# Sheet1.net
KiCad netlist of a schematic drawn in Altium Designer
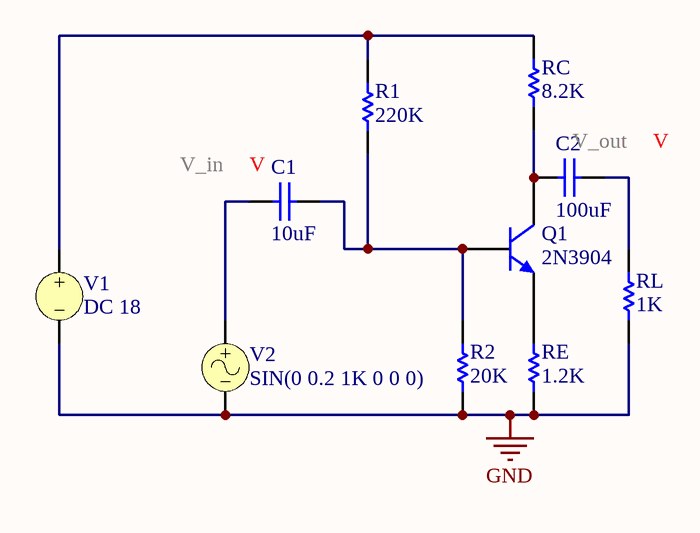
[diagram p0: Sheet1.SchDoc]

(export (version "E")
  (design (tool "Eeschema 10.0.6"))
  (components
    (comp (ref "C1")
      (value "10uF")
      (footprint "RAD-0.3")
      (description "Capacitor")
      (fields (field (name "PUBLISHER") "Altium Limited"))
      (libsource (lib "Miscellaneous Devices") (part "Cap"))
    )
    (comp (ref "C2")
      (value "100uF")
      (footprint "RAD-0.3")
      (description "Capacitor")
      (fields (field (name "PUBLISHER") "Altium Limited"))
      (libsource (lib "Miscellaneous Devices") (part "Cap"))
    )
    (comp (ref "Q1")
      (value "2N3904")
      (footprint "TO-92A")
      (description "NPN General Purpose Amplifier")
      (fields (field (name "PUBLISHER") "Altium Limited"))
      (libsource (lib "Miscellaneous Devices") (part "2N3904"))
    )
    (comp (ref "R1")
      (value "220K")
      (footprint "AXIAL-0.3")
      (description "Resistor")
      (fields (field (name "PUBLISHER") "Altium Limited"))
      (libsource (lib "Miscellaneous Devices") (part "Res1"))
    )
    (comp (ref "R2")
      (value "20K")
      (footprint "AXIAL-0.3")
      (description "Resistor")
      (fields (field (name "PUBLISHER") "Altium Limited"))
      (libsource (lib "Miscellaneous Devices") (part "Res1"))
    )
    (comp (ref "RC")
      (value "8.2K")
      (footprint "AXIAL-0.3")
      (description "Resistor")
      (fields (field (name "PUBLISHER") "Altium Limited"))
      (libsource (lib "Miscellaneous Devices") (part "Res1"))
    )
    (comp (ref "RE")
      (value "1.2K")
      (footprint "AXIAL-0.3")
      (description "Resistor")
      (fields (field (name "PUBLISHER") "Altium Limited"))
      (libsource (lib "Miscellaneous Devices") (part "Res1"))
    )
    (comp (ref "RL")
      (value "1K")
      (footprint "AXIAL-0.3")
      (description "Resistor")
      (fields (field (name "PUBLISHER") "Altium Limited"))
      (libsource (lib "Miscellaneous Devices") (part "Res1"))
    )
    (comp (ref "V1")
      (value "DC 18")
      (description "Voltage Source")
      (fields (field (name "PUBLISHER") "Altium Limited"))
      (libsource (lib "Simulation Generic Components") (part "VSRC"))
    )
    (comp (ref "V2")
      (value "SIN(0 0.2 1K 0 0 0)")
      (description "Sinusoidal Voltage Source")
      (fields (field (name "PUBLISHER") "Altium Limited"))
      (libsource (lib "Simulation Generic Components") (part "VSIN"))
    )
  )
  (nets
    (net (code "1") (name "GND") (class "Default")
      (node (ref "R2") (pin "1") (pinfunction "1_1") (pintype "passive"))
      (node (ref "RE") (pin "1") (pinfunction "1_1") (pintype "passive"))
      (node (ref "RL") (pin "1") (pinfunction "1_1") (pintype "passive"))
      (node (ref "V1") (pin "2") (pinfunction "2_2") (pintype "passive"))
      (node (ref "V2") (pin "2") (pinfunction "2_2") (pintype "passive"))
    )
    (net (code "2") (name "Net-(C1-Pad1)") (class "Default")
      (node (ref "C1") (pin "1") (pinfunction "1_1") (pintype "passive"))
      (node (ref "V2") (pin "1") (pinfunction "1_1") (pintype "passive"))
    )
    (net (code "3") (name "Net-(C2-Pad2)") (class "Default")
      (node (ref "C2") (pin "2") (pinfunction "2_2") (pintype "passive"))
      (node (ref "RL") (pin "2") (pinfunction "2_2") (pintype "passive"))
    )
    (net (code "4") (name "Net-(Q1-B)") (class "Default")
      (node (ref "C1") (pin "2") (pinfunction "2_2") (pintype "passive"))
      (node (ref "Q1") (pin "2") (pinfunction "B_2") (pintype "passive"))
      (node (ref "R1") (pin "1") (pinfunction "1_1") (pintype "passive"))
      (node (ref "R2") (pin "2") (pinfunction "2_2") (pintype "passive"))
    )
    (net (code "5") (name "Net-(Q1-C)") (class "Default")
      (node (ref "C2") (pin "1") (pinfunction "1_1") (pintype "passive"))
      (node (ref "Q1") (pin "3") (pinfunction "C_3") (pintype "passive"))
      (node (ref "RC") (pin "1") (pinfunction "1_1") (pintype "passive"))
    )
    (net (code "6") (name "Net-(Q1-E)") (class "Default")
      (node (ref "Q1") (pin "1") (pinfunction "E_1") (pintype "passive"))
      (node (ref "RE") (pin "2") (pinfunction "2_2") (pintype "passive"))
    )
    (net (code "7") (name "Net-(R1-Pad2)") (class "Default")
      (node (ref "R1") (pin "2") (pinfunction "2_2") (pintype "passive"))
      (node (ref "RC") (pin "2") (pinfunction "2_2") (pintype "passive"))
      (node (ref "V1") (pin "1") (pinfunction "1_1") (pintype "passive"))
    )
  )
)
